# Audio.net
KiCad netlist of a schematic drawn in Altium Designer
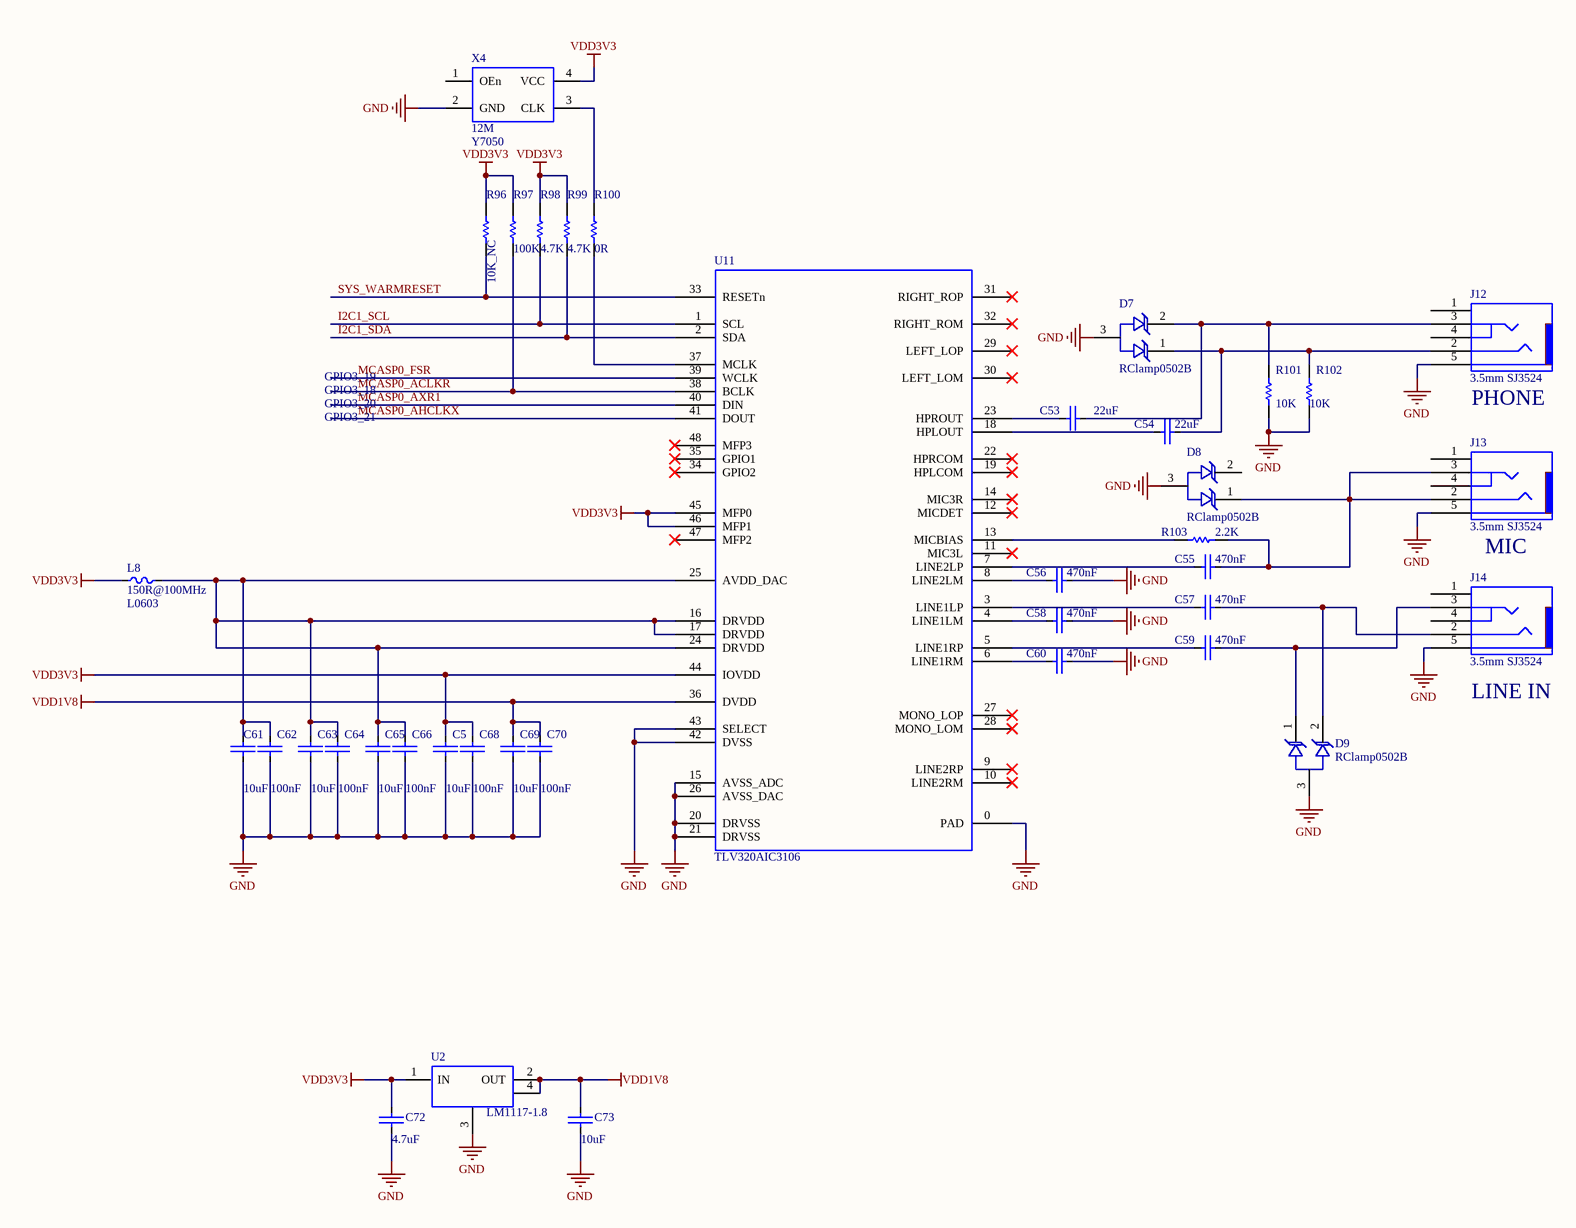
[diagram p0: Audio.SchDoc]

(export (version "E")
  (design (tool "Eeschema 10.0.6"))
  (components
    (comp (ref "C5") (value "10uF") (footprint "C0603_M1608") (libsource (lib "OK335xD") (part "CAP_1")))
    (comp (ref "C53") (value "22uF") (footprint "C1210_M3225") (libsource (lib "OK335xD") (part "CAP_1")))
    (comp (ref "C54") (value "22uF") (footprint "C1210_M3225") (libsource (lib "OK335xD") (part "CAP_1")))
    (comp (ref "C55") (value "470nF") (footprint "C0603_M1608") (libsource (lib "OK335xD") (part "CAP_1")))
    (comp (ref "C56") (value "470nF") (footprint "C0603_M1608") (libsource (lib "OK335xD") (part "CAP_1")))
    (comp (ref "C57") (value "470nF") (footprint "C0603_M1608") (libsource (lib "OK335xD") (part "CAP_1")))
    (comp (ref "C58") (value "470nF") (footprint "C0603_M1608") (libsource (lib "OK335xD") (part "CAP_1")))
    (comp (ref "C59") (value "470nF") (footprint "C0603_M1608") (libsource (lib "OK335xD") (part "CAP_1")))
    (comp (ref "C60") (value "470nF") (footprint "C0603_M1608") (libsource (lib "OK335xD") (part "CAP_1")))
    (comp (ref "C61") (value "10uF") (footprint "C0603_M1608") (libsource (lib "OK335xD") (part "CAP_1")))
    (comp (ref "C62") (value "100nF") (footprint "C0603_M1608") (libsource (lib "OK335xD") (part "CAP_1")))
    (comp (ref "C63") (value "10uF") (footprint "C0603_M1608") (libsource (lib "OK335xD") (part "CAP_1")))
    (comp (ref "C64") (value "100nF") (footprint "C0603_M1608") (libsource (lib "OK335xD") (part "CAP_1")))
    (comp (ref "C65") (value "10uF") (footprint "C0603_M1608") (libsource (lib "OK335xD") (part "CAP_1")))
    (comp (ref "C66") (value "100nF") (footprint "C0603_M1608") (libsource (lib "OK335xD") (part "CAP_1")))
    (comp (ref "C68") (value "100nF") (footprint "C0603_M1608") (libsource (lib "OK335xD") (part "CAP_1")))
    (comp (ref "C69") (value "10uF") (footprint "C0603_M1608") (libsource (lib "OK335xD") (part "CAP_1")))
    (comp (ref "C70") (value "100nF") (footprint "C0603_M1608") (libsource (lib "OK335xD") (part "CAP_1")))
    (comp (ref "C72") (value "4.7uF") (footprint "C0603_M1608") (libsource (lib "OK335xD") (part "CAP_1")))
    (comp (ref "C73") (value "10uF") (footprint "C0603_M1608") (libsource (lib "OK335xD") (part "CAP_1")))
    (comp (ref "D7")
      (value "RClamp0502B")
      (footprint "SOT-523")
      (fields (field (name "Comment") "LCTVS"))
      (libsource (lib "Sch") (part "LCTVS"))
    )
    (comp (ref "D8")
      (value "RClamp0502B")
      (footprint "SOT-523")
      (fields (field (name "Comment") "LCTVS"))
      (libsource (lib "Sch") (part "LCTVS"))
    )
    (comp (ref "D9")
      (value "RClamp0502B")
      (footprint "SOT-523")
      (fields (field (name "Comment") "LCTVS"))
      (libsource (lib "Sch") (part "LCTVS"))
    )
    (comp (ref "J12")
      (value "3.5mm SJ3524")
      (footprint "3.5mm SJ3524")
      (libsource (lib "OK335xD") (part "3.5mm SJ3524"))
    )
    (comp (ref "J13")
      (value "3.5mm SJ3524")
      (footprint "3.5mm SJ3524")
      (libsource (lib "OK335xD") (part "3.5mm SJ3524"))
    )
    (comp (ref "J14")
      (value "3.5mm SJ3524")
      (footprint "3.5mm SJ3524")
      (libsource (lib "OK335xD") (part "3.5mm SJ3524"))
    )
    (comp (ref "L8")
      (value "150R@100MHz")
      (footprint "L0603_M1608")
      (description "0603")
      (fields (field (name "ALTIUM_VALUE") "L0603"))
      (libsource (lib "S5PV210_core") (part "BEADS"))
    )
    (comp (ref "R96")
      (value "10K_NC")
      (footprint "R0603_M1608")
      (description "R0603")
      (fields (field (name "PUBLISHER") "Altium Limited"))
      (libsource (lib "Miscellaneous Devices") (part "Res1"))
    )
    (comp (ref "R97")
      (value "100K")
      (footprint "R0603_M1608")
      (description "R0603")
      (fields (field (name "PUBLISHER") "Altium Limited"))
      (libsource (lib "Miscellaneous Devices") (part "Res1"))
    )
    (comp (ref "R98")
      (value "4.7K")
      (footprint "R0603_M1608")
      (description "R0603")
      (fields (field (name "PUBLISHER") "Altium Limited"))
      (libsource (lib "Miscellaneous Devices") (part "Res1"))
    )
    (comp (ref "R99")
      (value "4.7K")
      (footprint "R0603_M1608")
      (description "R0603")
      (fields (field (name "PUBLISHER") "Altium Limited"))
      (libsource (lib "Miscellaneous Devices") (part "Res1"))
    )
    (comp (ref "R100")
      (value "0R")
      (footprint "R0603_M1608")
      (description "R0603")
      (fields (field (name "PUBLISHER") "Altium Limited"))
      (libsource (lib "Miscellaneous Devices") (part "Res1"))
    )
    (comp (ref "R101")
      (value "10K")
      (footprint "R0603_M1608")
      (description "R0603")
      (fields (field (name "PUBLISHER") "Altium Limited"))
      (libsource (lib "Miscellaneous Devices") (part "Res1"))
    )
    (comp (ref "R102")
      (value "10K")
      (footprint "R0603_M1608")
      (description "R0603")
      (fields (field (name "PUBLISHER") "Altium Limited"))
      (libsource (lib "Miscellaneous Devices") (part "Res1"))
    )
    (comp (ref "R103")
      (value "2.2K")
      (footprint "R0603_M1608")
      (description "R0603")
      (fields (field (name "PUBLISHER") "Altium Limited"))
      (libsource (lib "Miscellaneous Devices") (part "Res1"))
    )
    (comp (ref "U2")
      (value "LM1117-1.8")
      (footprint "LM1117")
      (fields (field (name "Comment") "LM1117"))
      (libsource (lib "Sch") (part "LM1117"))
    )
    (comp (ref "U11")
      (value "TLV320AIC3106")
      (footprint "QFN48(TLV320)")
      (description "AUDIO ENCODE")
      (libsource (lib "OK335xD") (part "TLV320AIC3106"))
    )
    (comp (ref "X4")
      (value "12M")
      (footprint "Y7050")
      (fields (field (name "ALTIUM_VALUE") "Y7050"))
      (libsource (lib "OK335xD") (part "12M XTAL"))
    )
  )
  (nets
    (net (code "1") (name "/I2C1_SCL") (class "Default")
      (node (ref "R98") (pin "1") (pinfunction "1_1") (pintype "passive"))
      (node (ref "U11") (pin "1") (pinfunction "SCL_1") (pintype "passive"))
    )
    (net (code "2") (name "/I2C1_SDA") (class "Default")
      (node (ref "R99") (pin "1") (pinfunction "1_1") (pintype "passive"))
      (node (ref "U11") (pin "2") (pinfunction "SDA_2") (pintype "passive"))
    )
    (net (code "3") (name "/MCASP0_ACLKR") (class "Default")
      (node (ref "R97") (pin "1") (pinfunction "1_1") (pintype "passive"))
      (node (ref "U11") (pin "38") (pinfunction "BCLK_38") (pintype "passive"))
    )
    (net (code "4") (name "/MCASP0_AHCLKX") (class "Default")
      (node (ref "U11") (pin "41") (pinfunction "DOUT_41") (pintype "passive"))
    )
    (net (code "5") (name "/MCASP0_AXR1") (class "Default")
      (node (ref "U11") (pin "40") (pinfunction "DIN_40") (pintype "passive"))
    )
    (net (code "6") (name "/MCASP0_FSR") (class "Default")
      (node (ref "U11") (pin "39") (pinfunction "WCLK_39") (pintype "passive"))
    )
    (net (code "7") (name "/SYS_WARMRESET") (class "Default")
      (node (ref "R96") (pin "1") (pinfunction "1_1") (pintype "passive"))
      (node (ref "U11") (pin "33") (pinfunction "RESETn_33") (pintype "passive"))
    )
    (net (code "8") (name "GND") (class "Default")
      (node (ref "C5") (pin "2") (pintype "passive"))
      (node (ref "C56") (pin "2") (pintype "passive"))
      (node (ref "C58") (pin "2") (pintype "passive"))
      (node (ref "C60") (pin "2") (pintype "passive"))
      (node (ref "C61") (pin "2") (pintype "passive"))
      (node (ref "C62") (pin "2") (pintype "passive"))
      (node (ref "C63") (pin "2") (pintype "passive"))
      (node (ref "C64") (pin "2") (pintype "passive"))
      (node (ref "C65") (pin "2") (pintype "passive"))
      (node (ref "C66") (pin "2") (pintype "passive"))
      (node (ref "C68") (pin "2") (pintype "passive"))
      (node (ref "C69") (pin "2") (pintype "passive"))
      (node (ref "C70") (pin "2") (pintype "passive"))
      (node (ref "C72") (pin "2") (pintype "passive"))
      (node (ref "C73") (pin "2") (pintype "passive"))
      (node (ref "D7") (pin "3") (pintype "passive"))
      (node (ref "D8") (pin "3") (pintype "passive"))
      (node (ref "D9") (pin "3") (pintype "passive"))
      (node (ref "J12") (pin "5") (pinfunction "5_5") (pintype "passive"))
      (node (ref "J13") (pin "5") (pinfunction "5_5") (pintype "passive"))
      (node (ref "J14") (pin "5") (pinfunction "5_5") (pintype "passive"))
      (node (ref "R101") (pin "1") (pinfunction "1_1") (pintype "passive"))
      (node (ref "R102") (pin "1") (pinfunction "1_1") (pintype "passive"))
      (node (ref "U11") (pin "0") (pinfunction "PAD_0") (pintype "passive"))
      (node (ref "U11") (pin "15") (pinfunction "AVSS_ADC_15") (pintype "passive"))
      (node (ref "U11") (pin "20") (pinfunction "DRVSS_20") (pintype "passive"))
      (node (ref "U11") (pin "21") (pinfunction "DRVSS_21") (pintype "passive"))
      (node (ref "U11") (pin "26") (pinfunction "AVSS_DAC_26") (pintype "passive"))
      (node (ref "U11") (pin "42") (pinfunction "DVSS_42") (pintype "passive"))
      (node (ref "U11") (pin "43") (pinfunction "SELECT_43") (pintype "passive"))
      (node (ref "U2") (pin "3") (pinfunction "GND_3") (pintype "passive"))
      (node (ref "X4") (pin "2") (pinfunction "GND_2") (pintype "passive"))
    )
    (net (code "9") (name "Net-(C53-Pad2)") (class "Default")
      (node (ref "C53") (pin "2") (pintype "passive"))
      (node (ref "D7") (pin "2") (pinfunction "2_2") (pintype "passive"))
      (node (ref "J12") (pin "3") (pinfunction "3_3") (pintype "passive"))
      (node (ref "R101") (pin "2") (pinfunction "2_2") (pintype "passive"))
    )
    (net (code "10") (name "Net-(C54-Pad2)") (class "Default")
      (node (ref "C54") (pin "2") (pintype "passive"))
      (node (ref "D7") (pin "1") (pinfunction "1_1") (pintype "passive"))
      (node (ref "J12") (pin "2") (pinfunction "2_2") (pintype "passive"))
      (node (ref "R102") (pin "2") (pinfunction "2_2") (pintype "passive"))
    )
    (net (code "11") (name "Net-(C55-Pad2)") (class "Default")
      (node (ref "C55") (pin "2") (pintype "passive"))
      (node (ref "D8") (pin "1") (pinfunction "1_1") (pintype "passive"))
      (node (ref "J13") (pin "2") (pinfunction "2_2") (pintype "passive"))
      (node (ref "J13") (pin "3") (pinfunction "3_3") (pintype "passive"))
      (node (ref "R103") (pin "1") (pinfunction "1_1") (pintype "passive"))
    )
    (net (code "12") (name "Net-(C57-Pad2)") (class "Default")
      (node (ref "C57") (pin "2") (pintype "passive"))
      (node (ref "D9") (pin "2") (pinfunction "2_2") (pintype "passive"))
      (node (ref "J14") (pin "2") (pinfunction "2_2") (pintype "passive"))
    )
    (net (code "13") (name "Net-(C59-Pad2)") (class "Default")
      (node (ref "C59") (pin "2") (pintype "passive"))
      (node (ref "D9") (pin "1") (pinfunction "1_1") (pintype "passive"))
      (node (ref "J14") (pin "3") (pinfunction "3_3") (pintype "passive"))
    )
    (net (code "14") (name "Net-(U11-AVDD_DAC)") (class "Default")
      (node (ref "C61") (pin "1") (pintype "passive"))
      (node (ref "C62") (pin "1") (pintype "passive"))
      (node (ref "C63") (pin "1") (pintype "passive"))
      (node (ref "C64") (pin "1") (pintype "passive"))
      (node (ref "C65") (pin "1") (pintype "passive"))
      (node (ref "C66") (pin "1") (pintype "passive"))
      (node (ref "L8") (pin "1") (pinfunction "1_1") (pintype "passive"))
      (node (ref "U11") (pin "16") (pinfunction "DRVDD_16") (pintype "passive"))
      (node (ref "U11") (pin "17") (pinfunction "DRVDD_17") (pintype "passive"))
      (node (ref "U11") (pin "24") (pinfunction "DRVDD_24") (pintype "passive"))
      (node (ref "U11") (pin "25") (pinfunction "AVDD_DAC_25") (pintype "passive"))
    )
    (net (code "15") (name "Net-(U11-HPLOUT)") (class "Default")
      (node (ref "C54") (pin "1") (pintype "passive"))
      (node (ref "U11") (pin "18") (pinfunction "HPLOUT_18") (pintype "passive"))
    )
    (net (code "16") (name "Net-(U11-HPROUT)") (class "Default")
      (node (ref "C53") (pin "1") (pintype "passive"))
      (node (ref "U11") (pin "23") (pinfunction "HPROUT_23") (pintype "passive"))
    )
    (net (code "17") (name "Net-(U11-LINE1LM)") (class "Default")
      (node (ref "C58") (pin "1") (pintype "passive"))
      (node (ref "U11") (pin "4") (pinfunction "LINE1LM_4") (pintype "passive"))
    )
    (net (code "18") (name "Net-(U11-LINE1LP)") (class "Default")
      (node (ref "C57") (pin "1") (pintype "passive"))
      (node (ref "U11") (pin "3") (pinfunction "LINE1LP_3") (pintype "passive"))
    )
    (net (code "19") (name "Net-(U11-LINE1RM)") (class "Default")
      (node (ref "C60") (pin "1") (pintype "passive"))
      (node (ref "U11") (pin "6") (pinfunction "LINE1RM_6") (pintype "passive"))
    )
    (net (code "20") (name "Net-(U11-LINE1RP)") (class "Default")
      (node (ref "C59") (pin "1") (pintype "passive"))
      (node (ref "U11") (pin "5") (pinfunction "LINE1RP_5") (pintype "passive"))
    )
    (net (code "21") (name "Net-(U11-LINE2LM)") (class "Default")
      (node (ref "C56") (pin "1") (pintype "passive"))
      (node (ref "U11") (pin "8") (pinfunction "LINE2LM_8") (pintype "passive"))
    )
    (net (code "22") (name "Net-(U11-LINE2LP)") (class "Default")
      (node (ref "C55") (pin "1") (pintype "passive"))
      (node (ref "U11") (pin "7") (pinfunction "LINE2LP_7") (pintype "passive"))
    )
    (net (code "23") (name "Net-(U11-MCLK)") (class "Default")
      (node (ref "R100") (pin "1") (pinfunction "1_1") (pintype "passive"))
      (node (ref "U11") (pin "37") (pinfunction "MCLK_37") (pintype "passive"))
    )
    (net (code "24") (name "Net-(U11-MICBIAS)") (class "Default")
      (node (ref "R103") (pin "2") (pinfunction "2_2") (pintype "passive"))
      (node (ref "U11") (pin "13") (pinfunction "MICBIAS_13") (pintype "passive"))
    )
    (net (code "25") (name "Net-(X4-CLK)") (class "Default")
      (node (ref "R100") (pin "2") (pinfunction "2_2") (pintype "passive"))
      (node (ref "X4") (pin "3") (pinfunction "CLK_3") (pintype "passive"))
    )
    (net (code "26") (name "VDD1V8") (class "Default")
      (node (ref "C69") (pin "1") (pintype "passive"))
      (node (ref "C70") (pin "1") (pintype "passive"))
      (node (ref "C73") (pin "1") (pintype "passive"))
      (node (ref "U11") (pin "36") (pinfunction "DVDD_36") (pintype "passive"))
      (node (ref "U2") (pin "2") (pinfunction "OUT_2") (pintype "passive"))
      (node (ref "U2") (pin "4") (pintype "passive"))
    )
    (net (code "27") (name "VDD3V3") (class "Default")
      (node (ref "C5") (pin "1") (pintype "passive"))
      (node (ref "C68") (pin "1") (pintype "passive"))
      (node (ref "C72") (pin "1") (pintype "passive"))
      (node (ref "L8") (pin "2") (pinfunction "2_2") (pintype "passive"))
      (node (ref "R96") (pin "2") (pinfunction "2_2") (pintype "passive"))
      (node (ref "R97") (pin "2") (pinfunction "2_2") (pintype "passive"))
      (node (ref "R98") (pin "2") (pinfunction "2_2") (pintype "passive"))
      (node (ref "R99") (pin "2") (pinfunction "2_2") (pintype "passive"))
      (node (ref "U11") (pin "44") (pinfunction "IOVDD_44") (pintype "passive"))
      (node (ref "U11") (pin "45") (pinfunction "MFP0_45") (pintype "passive"))
      (node (ref "U11") (pin "46") (pinfunction "MFP1_46") (pintype "passive"))
      (node (ref "U2") (pin "1") (pinfunction "IN_1") (pintype "passive"))
      (node (ref "X4") (pin "4") (pinfunction "VCC_4") (pintype "passive"))
    )
    (net (code "28") (name "unconnected-(D8-Pad2)") (class "Default")
      (node (ref "D8") (pin "2") (pinfunction "2_2") (pintype "passive"))
    )
    (net (code "29") (name "unconnected-(J12-Pad1)") (class "Default")
      (node (ref "J12") (pin "1") (pinfunction "1_1") (pintype "passive"))
    )
    (net (code "30") (name "unconnected-(J12-Pad4)") (class "Default")
      (node (ref "J12") (pin "4") (pinfunction "4_4") (pintype "passive"))
    )
    (net (code "31") (name "unconnected-(J13-Pad1)") (class "Default")
      (node (ref "J13") (pin "1") (pinfunction "1_1") (pintype "passive"))
    )
    (net (code "32") (name "unconnected-(J13-Pad4)") (class "Default")
      (node (ref "J13") (pin "4") (pinfunction "4_4") (pintype "passive"))
    )
    (net (code "33") (name "unconnected-(J14-Pad1)") (class "Default")
      (node (ref "J14") (pin "1") (pinfunction "1_1") (pintype "passive"))
    )
    (net (code "34") (name "unconnected-(J14-Pad4)") (class "Default")
      (node (ref "J14") (pin "4") (pinfunction "4_4") (pintype "passive"))
    )
    (net (code "35") (name "unconnected-(U11-GPIO1-Pad35)") (class "Default")
      (node (ref "U11") (pin "35") (pinfunction "GPIO1_35") (pintype "passive+no_connect"))
    )
    (net (code "36") (name "unconnected-(U11-GPIO2-Pad34)") (class "Default")
      (node (ref "U11") (pin "34") (pinfunction "GPIO2_34") (pintype "passive+no_connect"))
    )
    (net (code "37") (name "unconnected-(U11-HPLCOM-Pad19)") (class "Default")
      (node (ref "U11") (pin "19") (pinfunction "HPLCOM_19") (pintype "passive+no_connect"))
    )
    (net (code "38") (name "unconnected-(U11-HPRCOM-Pad22)") (class "Default")
      (node (ref "U11") (pin "22") (pinfunction "HPRCOM_22") (pintype "passive+no_connect"))
    )
    (net (code "39") (name "unconnected-(U11-LEFT_LOM-Pad30)") (class "Default")
      (node (ref "U11") (pin "30") (pinfunction "LEFT_LOM_30") (pintype "passive+no_connect"))
    )
    (net (code "40") (name "unconnected-(U11-LEFT_LOP-Pad29)") (class "Default")
      (node (ref "U11") (pin "29") (pinfunction "LEFT_LOP_29") (pintype "passive+no_connect"))
    )
    (net (code "41") (name "unconnected-(U11-LINE2RM-Pad10)") (class "Default")
      (node (ref "U11") (pin "10") (pinfunction "LINE2RM_10") (pintype "passive+no_connect"))
    )
    (net (code "42") (name "unconnected-(U11-LINE2RP-Pad9)") (class "Default")
      (node (ref "U11") (pin "9") (pinfunction "LINE2RP_9") (pintype "passive+no_connect"))
    )
    (net (code "43") (name "unconnected-(U11-MFP2-Pad47)") (class "Default")
      (node (ref "U11") (pin "47") (pinfunction "MFP2_47") (pintype "passive+no_connect"))
    )
    (net (code "44") (name "unconnected-(U11-MFP3-Pad48)") (class "Default")
      (node (ref "U11") (pin "48") (pinfunction "MFP3_48") (pintype "passive+no_connect"))
    )
    (net (code "45") (name "unconnected-(U11-MIC3L-Pad11)") (class "Default")
      (node (ref "U11") (pin "11") (pinfunction "MIC3L_11") (pintype "passive+no_connect"))
    )
    (net (code "46") (name "unconnected-(U11-MIC3R-Pad14)") (class "Default")
      (node (ref "U11") (pin "14") (pinfunction "MIC3R_14") (pintype "passive+no_connect"))
    )
    (net (code "47") (name "unconnected-(U11-MICDET-Pad12)") (class "Default")
      (node (ref "U11") (pin "12") (pinfunction "MICDET_12") (pintype "passive+no_connect"))
    )
    (net (code "48") (name "unconnected-(U11-MONO_LOM-Pad28)") (class "Default")
      (node (ref "U11") (pin "28") (pinfunction "MONO_LOM_28") (pintype "passive+no_connect"))
    )
    (net (code "49") (name "unconnected-(U11-MONO_LOP-Pad27)") (class "Default")
      (node (ref "U11") (pin "27") (pinfunction "MONO_LOP_27") (pintype "passive+no_connect"))
    )
    (net (code "50") (name "unconnected-(U11-RIGHT_ROM-Pad32)") (class "Default")
      (node (ref "U11") (pin "32") (pinfunction "RIGHT_ROM_32") (pintype "passive+no_connect"))
    )
    (net (code "51") (name "unconnected-(U11-RIGHT_ROP-Pad31)") (class "Default")
      (node (ref "U11") (pin "31") (pinfunction "RIGHT_ROP_31") (pintype "passive+no_connect"))
    )
    (net (code "52") (name "unconnected-(X4-OEn-Pad1)") (class "Default")
      (node (ref "X4") (pin "1") (pinfunction "OEn_1") (pintype "passive"))
    )
  )
)
